# 4layer_schematic.net
KiCad netlist of a schematic drawn in Altium Designer
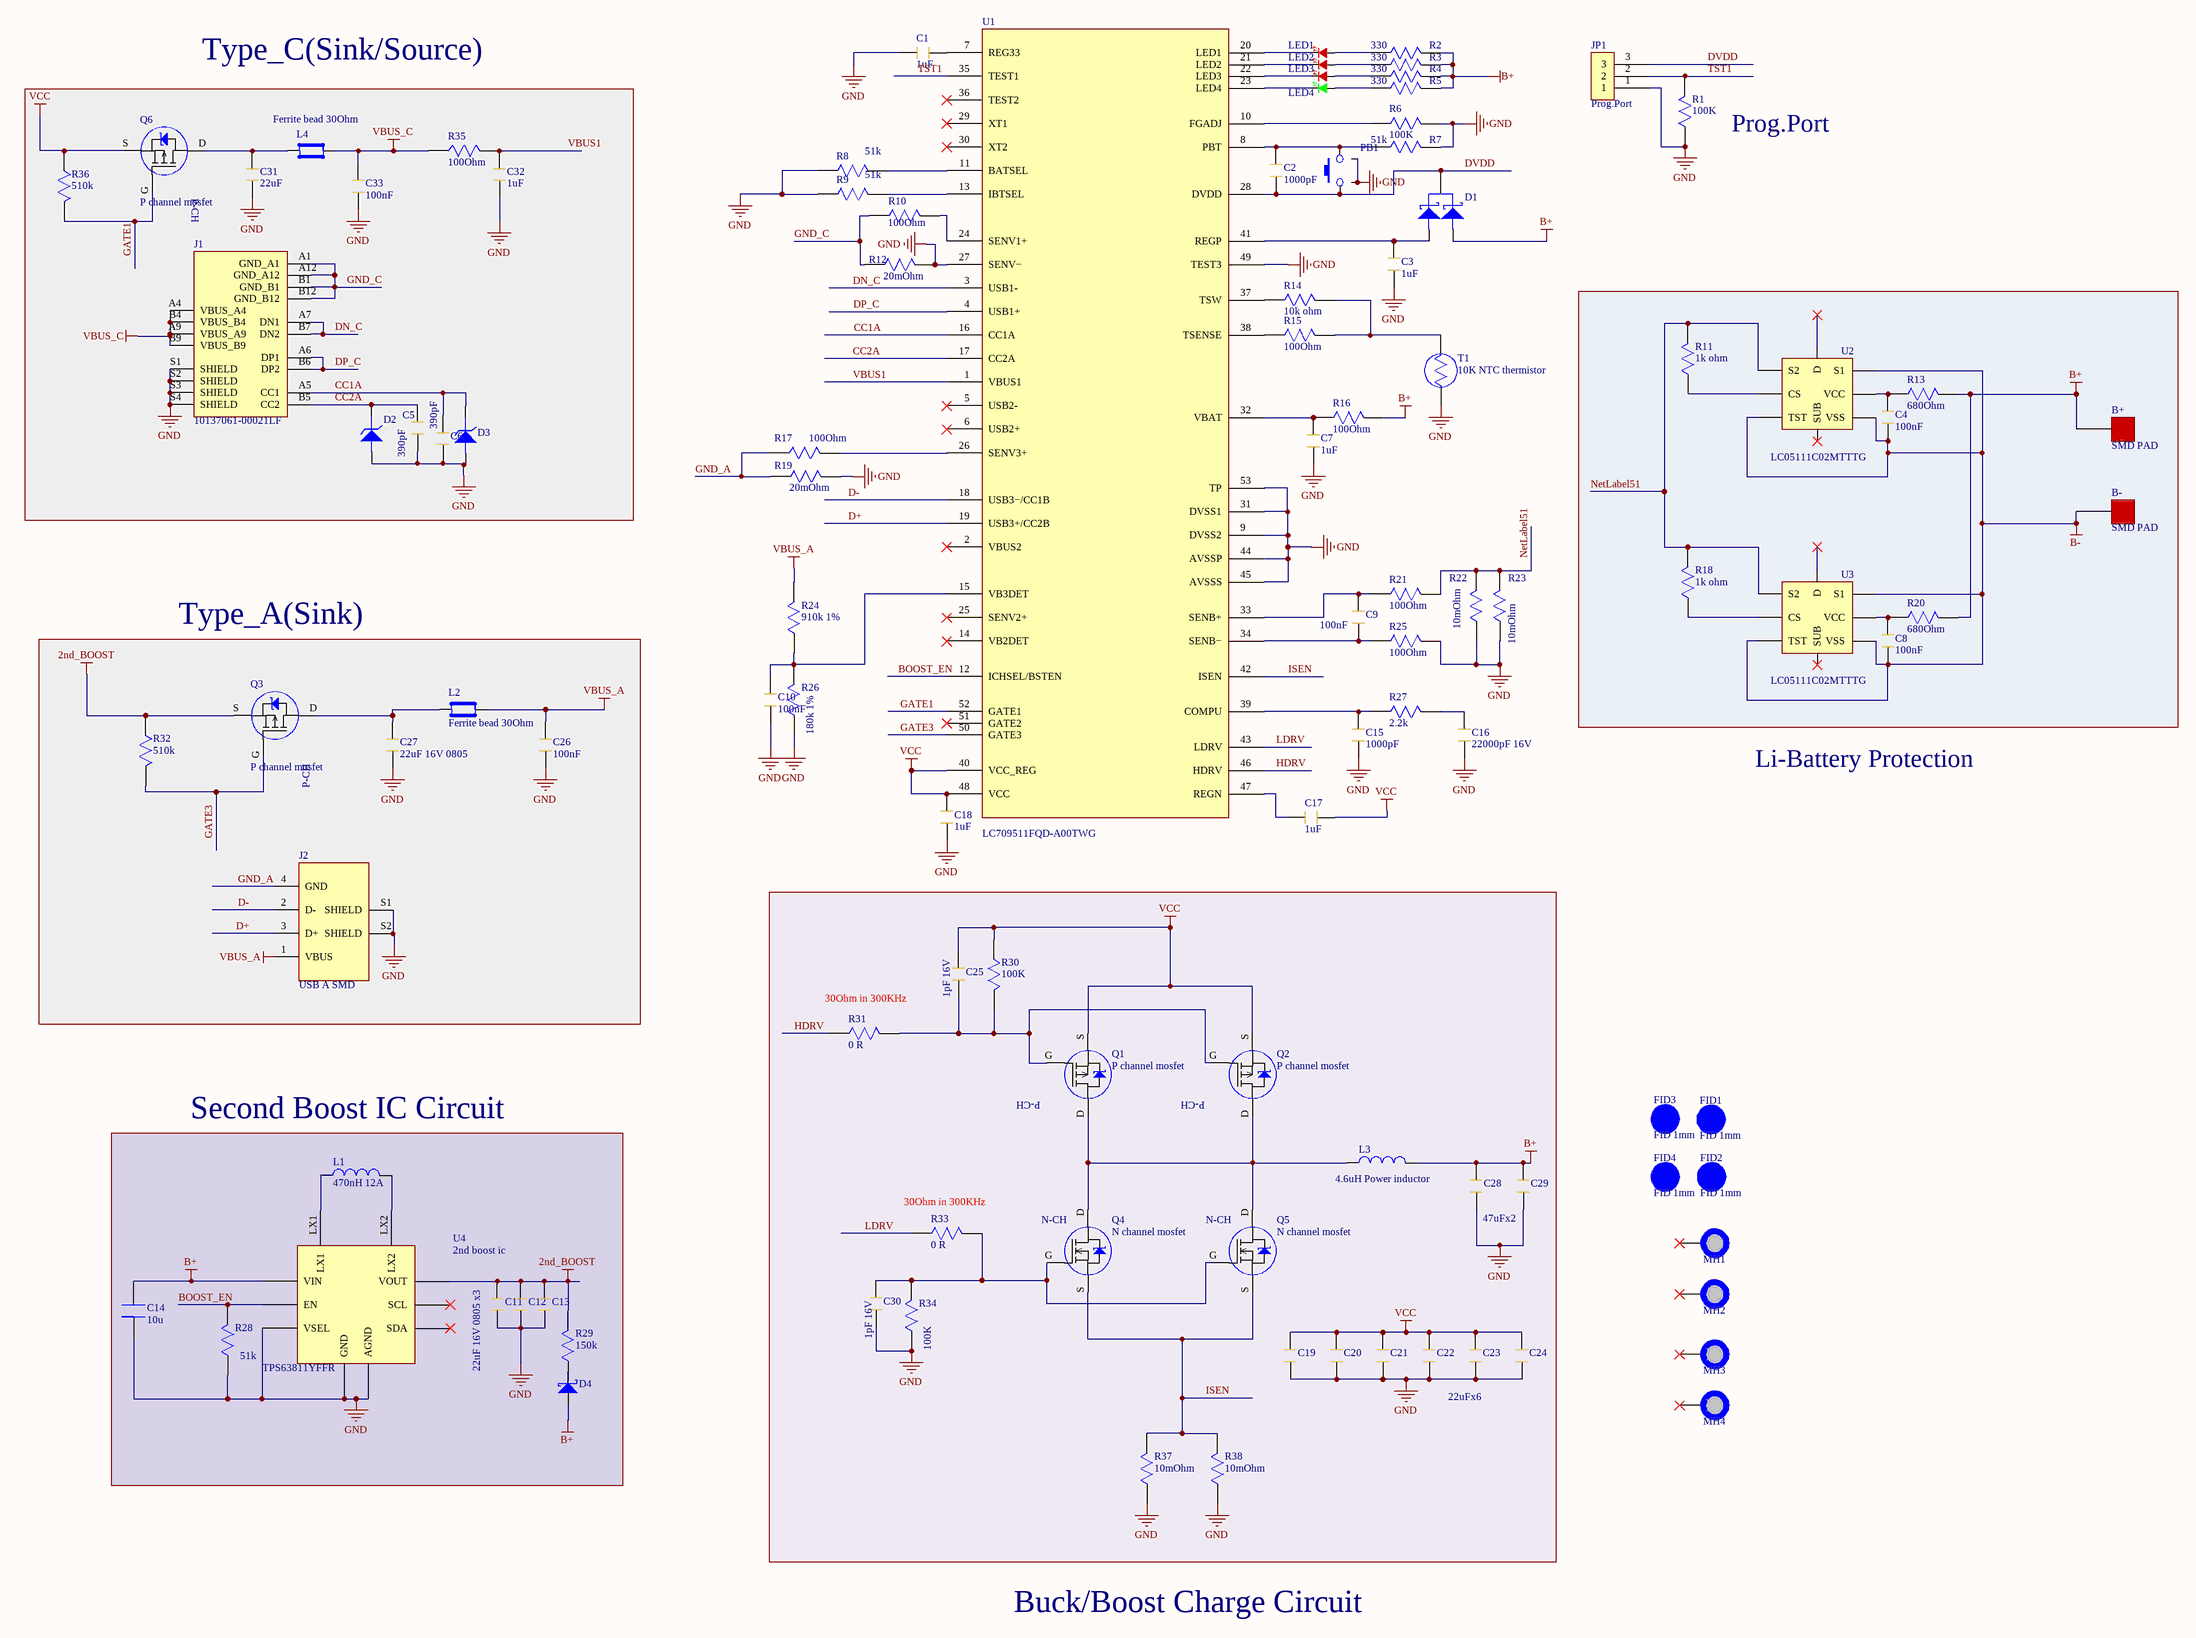
[diagram p0: 4layer schematic.SchDoc]

(export (version "E")
  (design (tool "Eeschema 10.0.6"))
  (components
    (comp (ref "B+")
      (value "SMD PAD")
      (footprint "SMD PAD")
      (libsource (lib "SchlibUltimate (2)") (part "SMD PAD"))
    )
    (comp (ref "B-")
      (value "SMD PAD")
      (footprint "SMD PAD")
      (libsource (lib "SchlibUltimate (2)") (part "SMD PAD"))
    )
    (comp (ref "C1")
      (value "1uF")
      (footprint "R0603")
      (description "Cap Ceramic 1uF 16V Y5V -20% to 80% SMD 0603 85C T/R")
      (fields (field (name "TOLERANCE") "80%"))
      (libsource (lib "SchlibUltimate (2)") (part "1uF cap"))
    )
    (comp (ref "C2")
      (value "1000pF")
      (footprint "C0402")
      (description "Cap Ceramic 0.001uF 16V X7R 10% Pad SMD 0402 125C T/R")
      (fields (field (name "TOLERANCE") "10%"))
      (libsource (lib "SchlibUltimate (2)") (part "1000pF cap"))
    )
    (comp (ref "C3")
      (value "1uF")
      (footprint "R0603")
      (description "Cap Ceramic 1uF 16V Y5V -20% to 80% SMD 0603 85C T/R")
      (fields (field (name "TOLERANCE") "80%"))
      (libsource (lib "SchlibUltimate (2)") (part "1uF cap"))
    )
    (comp (ref "C4")
      (value "100nF")
      (footprint "C0402")
      (description "Cap Ceramic 0.1uF 16V X7R 10% SMD 0402 125C Paper T/R")
      (fields (field (name "TOLERANCE") "10%"))
      (libsource (lib "SchlibUltimate (2)") (part "0.1uF cap"))
    )
    (comp (ref "C5")
      (value "390pF")
      (footprint "R0603")
      (description "Cap Ceramic 390pF 16V X7R 10% SMD 0201 125C Paper T/R")
      (fields (field (name "TOLERANCE") "10%"))
      (libsource (lib "SchlibUltimate (2)") (part "390pF smd cap"))
    )
    (comp (ref "C6")
      (value "390pF")
      (footprint "R0603")
      (description "Cap Ceramic 390pF 16V X7R 10% SMD 0201 125C Paper T/R")
      (fields (field (name "TOLERANCE") "10%"))
      (libsource (lib "SchlibUltimate (2)") (part "390pF smd cap"))
    )
    (comp (ref "C7")
      (value "1uF")
      (footprint "R0603")
      (description "Cap Ceramic 1uF 16V Y5V -20% to 80% SMD 0603 85C T/R")
      (fields (field (name "TOLERANCE") "80%"))
      (libsource (lib "SchlibUltimate (2)") (part "1uF cap"))
    )
    (comp (ref "C8")
      (value "100nF")
      (footprint "C0402")
      (description "Cap Ceramic 0.1uF 16V X7R 10% SMD 0402 125C Paper T/R")
      (fields (field (name "TOLERANCE") "10%"))
      (libsource (lib "SchlibUltimate (2)") (part "0.1uF cap"))
    )
    (comp (ref "C9")
      (value "100nF")
      (footprint "C0402")
      (description "Cap Ceramic 0.1uF 16V X7R 10% SMD 0402 125C Paper T/R")
      (fields (field (name "TOLERANCE") "10%"))
      (libsource (lib "SchlibUltimate (2)") (part "0.1uF cap"))
    )
    (comp (ref "C10")
      (value "100nF")
      (footprint "C0402")
      (description "Cap Ceramic 0.1uF 16V X7R 10% SMD 0402 125C Paper T/R")
      (fields (field (name "TOLERANCE") "10%"))
      (libsource (lib "SchlibUltimate (2)") (part "0.1uF cap"))
    )
    (comp (ref "C11")
      (value "22uF 16V 0805")
      (footprint "Cap 0805")
      (description "Cap Ceramic 22uF 16V X5R 20% Pad SMD 0805 85C T/R")
      (libsource (lib "SchlibUltimate (2)") (part "GRM21BR61C226ME44L"))
    )
    (comp (ref "C12")
      (value "22uF 16V 0805")
      (footprint "Cap 0805")
      (description "Cap Ceramic 22uF 16V X5R 20% Pad SMD 0805 85C T/R")
      (libsource (lib "SchlibUltimate (2)") (part "GRM21BR61C226ME44L"))
    )
    (comp (ref "C13")
      (value "22uF 16V 0805 x3")
      (footprint "Cap 0805")
      (description "Cap Ceramic 22uF 16V X5R 20% Pad SMD 0805 85C T/R")
      (libsource (lib "SchlibUltimate (2)") (part "GRM21BR61C226ME44L"))
    )
    (comp (ref "C14")
      (value "10u")
      (footprint "Cap 0805")
      (description "CAP CER 10UF 16V X5R 0805")
      (fields (field (name "TOLERANCE") "20%"))
      (libsource (lib "SchlibUltimate (2)") (part "C2012X5R1C106M125AC"))
    )
    (comp (ref "C15")
      (value "1000pF")
      (footprint "C0402")
      (description "Cap Ceramic 0.001uF 16V X7R 10% Pad SMD 0402 125C T/R")
      (fields (field (name "TOLERANCE") "10%"))
      (libsource (lib "SchlibUltimate (2)") (part "1000pF cap"))
    )
    (comp (ref "C16")
      (value "22000pF 16V")
      (footprint "C0402")
      (fields (field (name "TOLERANCE") "10%"))
      (libsource (lib "SchlibUltimate (2)") (part "22000pF cap"))
    )
    (comp (ref "C17")
      (value "1uF")
      (footprint "R0603")
      (description "Cap Ceramic 1uF 16V Y5V -20% to 80% SMD 0603 85C T/R")
      (fields (field (name "TOLERANCE") "80%"))
      (libsource (lib "SchlibUltimate (2)") (part "1uF cap"))
    )
    (comp (ref "C18")
      (value "1uF")
      (footprint "R0603")
      (description "Cap Ceramic 1uF 16V Y5V -20% to 80% SMD 0603 85C T/R")
      (fields (field (name "TOLERANCE") "80%"))
      (libsource (lib "SchlibUltimate (2)") (part "1uF cap"))
    )
    (comp (ref "C19")
      (value "22uF 16V 0805")
      (footprint "Cap 0805")
      (description "Cap Ceramic 22uF 16V X5R 20% Pad SMD 0805 85C T/R")
      (libsource (lib "SchlibUltimate (2)") (part "GRM21BR61C226ME44L"))
    )
    (comp (ref "C20")
      (value "22uF 16V 0805")
      (footprint "Cap 0805")
      (description "Cap Ceramic 22uF 16V X5R 20% Pad SMD 0805 85C T/R")
      (libsource (lib "SchlibUltimate (2)") (part "GRM21BR61C226ME44L"))
    )
    (comp (ref "C21")
      (value "22uF 16V 0805")
      (footprint "Cap 0805")
      (description "Cap Ceramic 22uF 16V X5R 20% Pad SMD 0805 85C T/R")
      (libsource (lib "SchlibUltimate (2)") (part "GRM21BR61C226ME44L"))
    )
    (comp (ref "C22")
      (value "22uF 16V 0805")
      (footprint "Cap 0805")
      (description "Cap Ceramic 22uF 16V X5R 20% Pad SMD 0805 85C T/R")
      (libsource (lib "SchlibUltimate (2)") (part "GRM21BR61C226ME44L"))
    )
    (comp (ref "C23")
      (value "22uF 16V 0805")
      (footprint "Cap 0805")
      (description "Cap Ceramic 22uF 16V X5R 20% Pad SMD 0805 85C T/R")
      (libsource (lib "SchlibUltimate (2)") (part "GRM21BR61C226ME44L"))
    )
    (comp (ref "C24")
      (value "22uF 16V 0805")
      (footprint "Cap 0805")
      (description "Cap Ceramic 22uF 16V X5R 20% Pad SMD 0805 85C T/R")
      (libsource (lib "SchlibUltimate (2)") (part "GRM21BR61C226ME44L"))
    )
    (comp (ref "C25")
      (value "1pF 16V")
      (footprint "C0402")
      (description "WURTH ELEKTRONIK - 885012005019 - CAP, 1PF, 16V, C0G/NP0, 0402")
      (libsource (lib "SchlibUltimate (2)") (part "1pF 16V cap"))
    )
    (comp (ref "C26")
      (value "100nF")
      (footprint "Cap 0805")
      (description "CAP CER 0.1UF 50V X7R 0805")
      (fields (field (name "TOLERANCE") "10%") (field (name "VOLTAGE") "50V"))
      (libsource (lib "SchlibUltimate (2)") (part "C2012X7R1H104K085AA"))
    )
    (comp (ref "C27")
      (value "22uF 16V 0805")
      (footprint "Cap 0805")
      (description "Cap Ceramic 22uF 16V X5R 20% Pad SMD 0805 85C T/R")
      (libsource (lib "SchlibUltimate (2)") (part "GRM21BR61C226ME44L"))
    )
    (comp (ref "C28")
      (value "47uFx2")
      (footprint "C1210")
      (description "KEMET - C1210C476M4PACTU. - CAPACITOR CERAMIC 47UF, 16V, X5R, 1210")
      (fields (field (name "TOLERANCE") "20%") (field (name "VOLTAGE") "16V"))
      (libsource (lib "SchlibUltimate (2)") (part "47uF cap"))
    )
    (comp (ref "C29")
      (value "47uF 16V")
      (footprint "C1210")
      (description "KEMET - C1210C476M4PACTU. - CAPACITOR CERAMIC 47UF, 16V, X5R, 1210")
      (fields (field (name "TOLERANCE") "20%") (field (name "VOLTAGE") "16V"))
      (libsource (lib "SchlibUltimate (2)") (part "47uF cap"))
    )
    (comp (ref "C30")
      (value "1pF 16V")
      (footprint "C0402")
      (description "WURTH ELEKTRONIK - 885012005019 - CAP, 1PF, 16V, C0G/NP0, 0402")
      (libsource (lib "SchlibUltimate (2)") (part "1pF 16V cap"))
    )
    (comp (ref "C31")
      (value "22uF")
      (footprint "Cap 0805")
      (description "Cap Ceramic 22uF 16V X5R 20% Pad SMD 0805 85C T/R")
      (libsource (lib "SchlibUltimate (2)") (part "GRM21BR61C226ME44L"))
    )
    (comp (ref "C32")
      (value "1uF")
      (footprint "R0603")
      (description "Cap Ceramic 1uF 16V Y5V -20% to 80% SMD 0603 85C T/R")
      (fields (field (name "TOLERANCE") "80%"))
      (libsource (lib "SchlibUltimate (2)") (part "1uF cap"))
    )
    (comp (ref "C33")
      (value "100nF")
      (footprint "Cap 0805")
      (description "CAP CER 0.1UF 50V X7R 0805")
      (fields (field (name "TOLERANCE") "10%") (field (name "VOLTAGE") "50V"))
      (libsource (lib "SchlibUltimate (2)") (part "C2012X7R1H104K085AA"))
    )
    (comp (ref "D1")
      (value "common cathode Schottkey")
      (footprint "3Pins schottkey")
      (description "Diode Schottky 30V 0.2A 3-Pin SOT-23 T/R")
      (libsource (lib "SchlibUltimate (2)") (part "3pins schottkey common cathode"))
    )
    (comp (ref "D2")
      (value "zener SOD532 5.1V 10mA")
      (footprint "Zener SOD532")
      (fields (field (name "TOLERANCE") "6%"))
      (libsource (lib "SchlibUltimate (2)") (part "MM5Z5V1T1G"))
    )
    (comp (ref "D3")
      (value "zener SOD532 5.1V 10mA")
      (footprint "Zener SOD532")
      (fields (field (name "TOLERANCE") "6%"))
      (libsource (lib "SchlibUltimate (2)") (part "MM5Z5V1T1G"))
    )
    (comp (ref "D4")
      (value "BAT54HT1G")
      (footprint "diode sfmntd")
      (description "DIODE SCHOTTKY 30V 200MA SOD323")
      (libsource (lib "SchlibUltimate (2)") (part "BAT54HT1G"))
    )
    (comp (ref "FID1")
      (value "FID 1mm")
      (footprint "FID")
      (libsource (lib "SchlibUltimate (2)") (part "FID 1mm"))
    )
    (comp (ref "FID2")
      (value "FID 1mm")
      (footprint "FID")
      (libsource (lib "SchlibUltimate (2)") (part "FID 1mm"))
    )
    (comp (ref "FID3")
      (value "FID 1mm")
      (footprint "FID")
      (libsource (lib "SchlibUltimate (2)") (part "FID 1mm"))
    )
    (comp (ref "FID4")
      (value "FID 1mm")
      (footprint "FID")
      (libsource (lib "SchlibUltimate (2)") (part "FID 1mm"))
    )
    (comp (ref "J1")
      (value "10137061-00021LF")
      (footprint "PCBComponent_1")
      (description "Conn USB 3.1 Type C RCP 24 POS 0.5mm Solder RA SMF 24 Terminal 1 Port T/R")
      (libsource (lib "SchlibUltimate (2)") (part "10137061-00021LF"))
    )
    (comp (ref "J2")
      (value "USB A SMD")
      (footprint "692122030100")
      (description "Socket, angled USB 3.0 A   9 P, 692122030100, Würth Elektronik")
      (libsource (lib "SchlibUltimate (2)") (part "USB A SMD"))
    )
    (comp (ref "JP1")
      (value "Prog.Port")
      (footprint "HDR Male 1x3")
      (description "CONN HEADER VERT 3POS 2.54MM")
      (libsource (lib "SchlibUltimate (2)") (part "68000-103HLF"))
    )
    (comp (ref "L1")
      (value "470nH 12A")
      (footprint "inductor 470nH")
      (libsource (lib "SchlibUltimate (2)") (part "470nH ind"))
    )
    (comp (ref "L2")
      (value "Ferrite bead 30Ohm")
      (footprint "R0805")
      (description "Ferrite Beads Multi-Layer 30Ohm 100MHz 4A 14mOhm DCR 0805 T/R")
      (fields (field (name "TOLERANCE") "25%"))
      (libsource (lib "SchlibUltimate (2)") (part "BLM21PG300SN1D"))
    )
    (comp (ref "L3")
      (value "4.6uH Power inductor")
      (footprint "inductor mouser")
      (description "FIXED IND 4.6UH 9.1A 13.8 MOHM")
      (fields (field (name "TOLERANCE") "30%"))
      (libsource (lib "SchlibUltimate (2)") (part "CDRH127/LDNP-4R6NC"))
    )
    (comp (ref "L4")
      (value "Ferrite bead 30Ohm")
      (footprint "R0805")
      (description "Ferrite Beads Multi-Layer 30Ohm 100MHz 4A 14mOhm DCR 0805 T/R")
      (fields (field (name "TOLERANCE") "25%"))
      (libsource (lib "SchlibUltimate (2)") (part "BLM21PG300SN1D"))
    )
    (comp (ref "LED1")
      (value "RED SMD")
      (footprint "ORNG LED SMD 1206")
      (description "LED RED CLEAR 1206 SMD")
      (libsource (lib "SchlibUltimate (2)") (part "SMLLX1206ICTR"))
    )
    (comp (ref "LED2")
      (value "RED SMD")
      (footprint "ORNG LED SMD 1206")
      (description "LED RED CLEAR 1206 SMD")
      (libsource (lib "SchlibUltimate (2)") (part "SMLLX1206ICTR"))
    )
    (comp (ref "LED3")
      (value "RED SMD")
      (footprint "ORNG LED SMD 1206")
      (description "LED RED CLEAR 1206 SMD")
      (libsource (lib "SchlibUltimate (2)") (part "SMLLX1206ICTR"))
    )
    (comp (ref "LED4")
      (value "GRN SMD")
      (footprint "GRN SMD LED")
      (description "Led Green SMD")
      (libsource (lib "SchlibUltimate (2)") (part "LNJ311G83RA"))
    )
    (comp (ref "MH1")
      (value "Mount holes")
      (footprint "MH")
      (libsource (lib "SchlibUltimate (2)") (part "Mount holes"))
    )
    (comp (ref "MH2")
      (value "Mount holes")
      (footprint "MH")
      (libsource (lib "SchlibUltimate (2)") (part "Mount holes"))
    )
    (comp (ref "MH3")
      (value "MH. not plated")
      (footprint "MH. not plated")
      (libsource (lib "SchlibUltimate (2)") (part "MH. not plated"))
    )
    (comp (ref "MH4")
      (value "MH. not plated")
      (footprint "MH. not plated")
      (libsource (lib "SchlibUltimate (2)") (part "MH. not plated"))
    )
    (comp (ref "PB1")
      (value "FSMRA4JH04")
      (footprint "PB Right angle through hole")
      (description "TE CONNECTIVITY - FSMRA4JH04 - SWITCH, TACT, SPST")
      (libsource (lib "SchlibUltimate (2)") (part "FSMRA4JH04"))
    )
    (comp (ref "Q1")
      (value "P channel mosfet")
      (footprint "ECH8310-TL-H")
      (description "Trans MOSFET P-CH 30V 9A 8-Pin ECH T/R")
      (libsource (lib "SchlibUltimate (2)") (part "ECH8310-TL-H"))
    )
    (comp (ref "Q2")
      (value "P channel mosfet")
      (footprint "ECH8310-TL-H")
      (description "Trans MOSFET P-CH 30V 9A 8-Pin ECH T/R")
      (libsource (lib "SchlibUltimate (2)") (part "ECH8310-TL-H"))
    )
    (comp (ref "Q3")
      (value "P channel mosfet")
      (footprint "ECH8310-TL-H")
      (description "Trans MOSFET P-CH 30V 9A 8-Pin ECH T/R")
      (libsource (lib "SchlibUltimate (2)") (part "ECH8310-TL-H"))
    )
    (comp (ref "Q4")
      (value "N channel mosfet")
      (footprint "Power mosfet on semi")
      (description "Single N−Channel Power MOSFET 25V, 94A, 3.3mΩ")
      (libsource (lib "SchlibUltimate (2)") (part "NTTFS4H05NTAG"))
    )
    (comp (ref "Q5")
      (value "N channel mosfet")
      (footprint "Power mosfet on semi")
      (description "Single N−Channel Power MOSFET 25V, 94A, 3.3mΩ")
      (libsource (lib "SchlibUltimate (2)") (part "NTTFS4H05NTAG"))
    )
    (comp (ref "Q6")
      (value "P channel mosfet")
      (footprint "ECH8310-TL-H")
      (description "Trans MOSFET P-CH 30V 9A 8-Pin ECH T/R")
      (libsource (lib "SchlibUltimate (2)") (part "ECH8310-TL-H"))
    )
    (comp (ref "R1")
      (value "100K")
      (footprint "R0805")
      (description "RES SMD 100K OHM 1% 1/8W 0805")
      (fields (field (name "TOLERANCE") "1%"))
      (libsource (lib "SchlibUltimate (2)") (part "RC0805FR-07100KL"))
    )
    (comp (ref "R2")
      (value "330")
      (footprint "R0805")
      (description "YAGEO   RC0805JR-07330RL   THICK FILM RESISTOR, 330 OHM, 125mW, 5%, FULL REEL")
      (fields (field (name "TOLERANCE") "5%"))
      (libsource (lib "SchlibUltimate (2)") (part "RC0805JR-07330RL"))
    )
    (comp (ref "R3")
      (value "330")
      (footprint "R0805")
      (description "YAGEO   RC0805JR-07330RL   THICK FILM RESISTOR, 330 OHM, 125mW, 5%, FULL REEL")
      (fields (field (name "TOLERANCE") "5%"))
      (libsource (lib "SchlibUltimate (2)") (part "RC0805JR-07330RL"))
    )
    (comp (ref "R4")
      (value "330")
      (footprint "R0805")
      (description "YAGEO   RC0805JR-07330RL   THICK FILM RESISTOR, 330 OHM, 125mW, 5%, FULL REEL")
      (fields (field (name "TOLERANCE") "5%"))
      (libsource (lib "SchlibUltimate (2)") (part "RC0805JR-07330RL"))
    )
    (comp (ref "R5")
      (value "330")
      (footprint "R0805")
      (description "YAGEO   RC0805JR-07330RL   THICK FILM RESISTOR, 330 OHM, 125mW, 5%, FULL REEL")
      (fields (field (name "TOLERANCE") "5%"))
      (libsource (lib "SchlibUltimate (2)") (part "RC0805JR-07330RL"))
    )
    (comp (ref "R6")
      (value "100K")
      (footprint "R0805")
      (description "RES SMD 100K OHM 1% 1/8W 0805")
      (fields (field (name "TOLERANCE") "1%"))
      (libsource (lib "SchlibUltimate (2)") (part "RC0805FR-07100KL"))
    )
    (comp (ref "R7")
      (value "51k")
      (footprint "R0805")
      (fields (field (name "TOLERANCE") "5%"))
      (libsource (lib "SchlibUltimate (2)") (part "CRCW080551K0JNEA"))
    )
    (comp (ref "R8")
      (value "51k")
      (footprint "R0805")
      (fields (field (name "TOLERANCE") "5%"))
      (libsource (lib "SchlibUltimate (2)") (part "CRCW080551K0JNEA"))
    )
    (comp (ref "R9")
      (value "51k")
      (footprint "R0805")
      (fields (field (name "TOLERANCE") "5%"))
      (libsource (lib "SchlibUltimate (2)") (part "CRCW080551K0JNEA"))
    )
    (comp (ref "R10")
      (value "100Ohm")
      (footprint "R0603")
      (fields (field (name "TOLERANCE") "5%"))
      (libsource (lib "SchlibUltimate (2)") (part "ESR03EZPJ101"))
    )
    (comp (ref "R11")
      (value "1k ohm")
      (footprint "R0805")
      (description "RES SMD 1K OHM 1% 1/8W 0805")
      (fields (field (name "TOLERANCE") "1%"))
      (libsource (lib "SchlibUltimate (2)") (part "RC0805FR-071KL"))
    )
    (comp (ref "R12")
      (value "20mOhm")
      (footprint "R1206")
      (fields (field (name "TOLERANCE") "1%"))
      (libsource (lib "SchlibUltimate (2)") (part "ERJ8CWFR020V"))
    )
    (comp (ref "R13")
      (value "680Ohm")
      (footprint "R0805")
      (fields (field (name "TOLERANCE") "1%"))
      (libsource (lib "SchlibUltimate (2)") (part "680Ohm 1/8 watt"))
    )
    (comp (ref "R14")
      (value "10k ohm")
      (footprint "R0805")
      (description "RES SMD 10K OHM 1% 1/8W 0805")
      (fields (field (name "TOLERANCE") "1%"))
      (libsource (lib "SchlibUltimate (2)") (part "RC0805FR-0710KL"))
    )
    (comp (ref "R15")
      (value "100Ohm")
      (footprint "R0603")
      (fields (field (name "TOLERANCE") "5%"))
      (libsource (lib "SchlibUltimate (2)") (part "ESR03EZPJ101"))
    )
    (comp (ref "R16")
      (value "100Ohm")
      (footprint "R0603")
      (fields (field (name "TOLERANCE") "5%"))
      (libsource (lib "SchlibUltimate (2)") (part "ESR03EZPJ101"))
    )
    (comp (ref "R17")
      (value "100Ohm")
      (footprint "R0603")
      (fields (field (name "TOLERANCE") "5%"))
      (libsource (lib "SchlibUltimate (2)") (part "ESR03EZPJ101"))
    )
    (comp (ref "R18")
      (value "1k ohm")
      (footprint "R0805")
      (description "RES SMD 1K OHM 1% 1/8W 0805")
      (fields (field (name "TOLERANCE") "1%"))
      (libsource (lib "SchlibUltimate (2)") (part "RC0805FR-071KL"))
    )
    (comp (ref "R19")
      (value "20mOhm")
      (footprint "R1206")
      (fields (field (name "TOLERANCE") "1%"))
      (libsource (lib "SchlibUltimate (2)") (part "ERJ8CWFR020V"))
    )
    (comp (ref "R20")
      (value "680Ohm")
      (footprint "R0805")
      (fields (field (name "TOLERANCE") "1%"))
      (libsource (lib "SchlibUltimate (2)") (part "680Ohm 1/8 watt"))
    )
    (comp (ref "R21")
      (value "100Ohm")
      (footprint "R0603")
      (fields (field (name "TOLERANCE") "5%"))
      (libsource (lib "SchlibUltimate (2)") (part "ESR03EZPJ101"))
    )
    (comp (ref "R22")
      (value "10mOhm")
      (footprint "R1206")
      (fields (field (name "TOLERANCE") "1%"))
      (libsource (lib "SchlibUltimate (2)") (part "ERJ-8BWFR010V"))
    )
    (comp (ref "R23")
      (value "10mOhm")
      (footprint "R1206")
      (fields (field (name "TOLERANCE") "1%"))
      (libsource (lib "SchlibUltimate (2)") (part "ERJ-8BWFR010V"))
    )
    (comp (ref "R24")
      (value "910k 1%")
      (footprint "R0805")
      (description "Res Thick Film 0805 9.1K Ohm 1% 1/8W +/-100ppm/ßC Molded SMD Punched Carrier T/R")
      (fields (field (name "TOLERANCE") "1%"))
      (libsource (lib "SchlibUltimate (2)") (part "ERJ-6ENF9101V"))
    )
    (comp (ref "R25")
      (value "100Ohm")
      (footprint "R0603")
      (fields (field (name "TOLERANCE") "5%"))
      (libsource (lib "SchlibUltimate (2)") (part "ESR03EZPJ101"))
    )
    (comp (ref "R26")
      (value "180k 1%")
      (footprint "R0805")
      (description "Thick Film Resistors - SMD 0805 180Kohms 1% AEC-Q200")
      (fields (field (name "TOLERANCE") "1%"))
      (libsource (lib "SchlibUltimate (2)") (part "ERJ-6ENF1803V"))
    )
    (comp (ref "R27")
      (value "2.2k")
      (footprint "R0805")
      (description "RESISTOR, THICK FILM, 2.2KOHM, 125mW, 1%, FULL REEL")
      (fields (field (name "TOLERANCE") "1%"))
      (libsource (lib "SchlibUltimate (2)") (part "RC0805FR-072K2L"))
    )
    (comp (ref "R28")
      (value "51k")
      (footprint "R0805")
      (fields (field (name "TOLERANCE") "5%"))
      (libsource (lib "SchlibUltimate (2)") (part "CRCW080551K0JNEA"))
    )
    (comp (ref "R29")
      (value "150k")
      (footprint "R0805")
      (description "RES SMD 150K OHM 5% 1/8W 0805")
      (fields (field (name "TOLERANCE") "5%"))
      (libsource (lib "SchlibUltimate (2)") (part "ERJ-6GEYJ154V"))
    )
    (comp (ref "R30")
      (value "100K")
      (footprint "R0805")
      (description "RES SMD 100K OHM 1% 1/8W 0805")
      (fields (field (name "TOLERANCE") "1%"))
      (libsource (lib "SchlibUltimate (2)") (part "RC0805FR-07100KL"))
    )
    (comp (ref "R31")
      (value "0 R")
      (footprint "R0805")
      (description "RES SMD 0 OHM JUMPER 1/8W 0805")
      (fields (field (name "TOLERANCE") "5%"))
      (libsource (lib "SchlibUltimate (2)") (part "RC0805JR-070RL"))
    )
    (comp (ref "R32")
      (value "510k")
      (footprint "R0805")
      (description "RES SMD 510K OHM 5% 1/8W 0805")
      (fields (field (name "TOLERANCE") "5%"))
      (libsource (lib "SchlibUltimate (2)") (part "ERJ-6GEYJ514V"))
    )
    (comp (ref "R33")
      (value "0 R")
      (footprint "R0805")
      (description "RES SMD 0 OHM JUMPER 1/8W 0805")
      (fields (field (name "TOLERANCE") "5%"))
      (libsource (lib "SchlibUltimate (2)") (part "RC0805JR-070RL"))
    )
    (comp (ref "R34")
      (value "100K")
      (footprint "R0805")
      (description "RES SMD 100K OHM 1% 1/8W 0805")
      (fields (field (name "TOLERANCE") "1%"))
      (libsource (lib "SchlibUltimate (2)") (part "RC0805FR-07100KL"))
    )
    (comp (ref "R35")
      (value "100Ohm")
      (footprint "R0603")
      (fields (field (name "TOLERANCE") "5%"))
      (libsource (lib "SchlibUltimate (2)") (part "ESR03EZPJ101"))
    )
    (comp (ref "R36")
      (value "510k")
      (footprint "R0805")
      (description "RES SMD 510K OHM 5% 1/8W 0805")
      (fields (field (name "TOLERANCE") "5%"))
      (libsource (lib "SchlibUltimate (2)") (part "ERJ-6GEYJ514V"))
    )
    (comp (ref "R37")
      (value "10mOhm")
      (footprint "R1206")
      (fields (field (name "TOLERANCE") "1%"))
      (libsource (lib "SchlibUltimate (2)") (part "ERJ-8BWFR010V"))
    )
    (comp (ref "R38")
      (value "10mOhm")
      (footprint "R1206")
      (fields (field (name "TOLERANCE") "1%"))
      (libsource (lib "SchlibUltimate (2)") (part "ERJ-8BWFR010V"))
    )
    (comp (ref "T1")
      (value "10K NTC thermistor")
      (footprint "thermistor")
      (description "Thermistor, High Sensitivity, NTC, Res 10 Kilohms, Tol +/-2%, Radial, Disc, TC 15Sec.")
      (fields (field (name "TOLERANCE") "2%"))
      (libsource (lib "SchlibUltimate (2)") (part "RL0503-5820-97-MS"))
    )
    (comp (ref "U1")
      (value "LC709511FQD-A00TWG")
      (footprint "Quad52")
      (description "Power Bank Controller, USB Type-C & Quick Charge™ 3.0, for 1-Cell Li-Ion and Li-Poly Battery")
      (fields (field (name "SUPPLIER PART NUMBER 1") "LC709511FQD-A00TWG"))
      (libsource (lib "SchlibUltimate (2)") (part "LC709511FQD-A00TWG"))
    )
    (comp (ref "U2")
      (value "LC05111C02MTTTG")
      (footprint "LC05111C02MTTTGOSCT")
      (description "IC BATT PROTECTION LI-ION 6WDFN")
      (libsource (lib "SchlibUltimate (2)") (part "LC05111C02MTTTG"))
    )
    (comp (ref "U3")
      (value "LC05111C02MTTTG")
      (footprint "LC05111C02MTTTGOSCT")
      (description "IC BATT PROTECTION LI-ION 6WDFN")
      (libsource (lib "SchlibUltimate (2)") (part "LC05111C02MTTTG"))
    )
    (comp (ref "U4")
      (value "2nd boost ic")
      (footprint "BGA3x5")
      (description "Switching mode BUCK/BOOST IC")
      (libsource (lib "SchlibUltimate (2)") (part "TPS63811YFFR"))
    )
  )
  (nets
    (net (code "1") (name "/BOOST_EN") (class "Default")
      (node (ref "R28") (pin "2") (pinfunction "2_2") (pintype "passive"))
      (node (ref "U1") (pin "12") (pinfunction "ICHSEL/BSTEN_12") (pintype "passive"))
      (node (ref "U4") (pin "EN") (pinfunction "EN_EN") (pintype "passive"))
    )
    (net (code "2") (name "/CC1A") (class "Default")
      (node (ref "C6") (pin "2") (pinfunction "2_2") (pintype "passive"))
      (node (ref "D3") (pin "1") (pinfunction "K_1") (pintype "passive"))
      (node (ref "J1") (pin "A5") (pinfunction "CC1_A5") (pintype "passive"))
      (node (ref "U1") (pin "16") (pinfunction "CC1A_16") (pintype "passive"))
    )
    (net (code "3") (name "/CC2A") (class "Default")
      (node (ref "C5") (pin "2") (pinfunction "2_2") (pintype "passive"))
      (node (ref "D2") (pin "1") (pinfunction "K_1") (pintype "passive"))
      (node (ref "J1") (pin "B5") (pinfunction "CC2_B5") (pintype "passive"))
      (node (ref "U1") (pin "17") (pinfunction "CC2A_17") (pintype "passive"))
    )
    (net (code "4") (name "/D+") (class "Default")
      (node (ref "J2") (pin "3") (pinfunction "D+_3") (pintype "passive"))
      (node (ref "U1") (pin "19") (pinfunction "USB3+/CC2B_19") (pintype "passive"))
    )
    (net (code "5") (name "/D-") (class "Default")
      (node (ref "J2") (pin "2") (pinfunction "D-_2") (pintype "passive"))
      (node (ref "U1") (pin "18") (pinfunction "USB3−/CC1B_18") (pintype "passive"))
    )
    (net (code "6") (name "/DN_C") (class "Default")
      (node (ref "J1") (pin "A7") (pinfunction "DN1_A7") (pintype "passive"))
      (node (ref "J1") (pin "B7") (pinfunction "DN2_B7") (pintype "passive"))
      (node (ref "U1") (pin "3") (pinfunction "USB1-_3") (pintype "passive"))
    )
    (net (code "7") (name "/DP_C") (class "Default")
      (node (ref "J1") (pin "A6") (pinfunction "DP1_A6") (pintype "passive"))
      (node (ref "J1") (pin "B6") (pinfunction "DP2_B6") (pintype "passive"))
      (node (ref "U1") (pin "4") (pinfunction "USB1+_4") (pintype "passive"))
    )
    (net (code "8") (name "/DVDD") (class "Default")
      (node (ref "C2") (pin "1") (pinfunction "1_1") (pintype "passive"))
      (node (ref "D1") (pin "3") (pinfunction "Cathode_3") (pintype "passive"))
      (node (ref "JP1") (pin "3") (pinfunction "3_3") (pintype "passive"))
      (node (ref "PB1") (pin "1") (pinfunction "1_1") (pintype "passive"))
      (node (ref "U1") (pin "28") (pinfunction "DVDD_28") (pintype "passive"))
    )
    (net (code "9") (name "/GATE1") (class "Default")
      (node (ref "Q6") (pin "G") (pinfunction "G_G") (pintype "passive"))
      (node (ref "R36") (pin "1") (pinfunction "1_1") (pintype "passive"))
      (node (ref "U1") (pin "52") (pinfunction "GATE1_52") (pintype "passive"))
    )
    (net (code "10") (name "/GATE3") (class "Default")
      (node (ref "Q3") (pin "G") (pinfunction "G_G") (pintype "passive"))
      (node (ref "R32") (pin "1") (pinfunction "1_1") (pintype "passive"))
      (node (ref "U1") (pin "50") (pinfunction "GATE3_50") (pintype "passive"))
    )
    (net (code "11") (name "/GND_A") (class "Default")
      (node (ref "J2") (pin "4") (pinfunction "GND_4") (pintype "passive"))
      (node (ref "R17") (pin "1") (pinfunction "1_1") (pintype "passive"))
      (node (ref "R19") (pin "1") (pinfunction "1_1") (pintype "passive"))
    )
    (net (code "12") (name "/GND_C") (class "Default")
      (node (ref "J1") (pin "A1") (pinfunction "GND_A1_A1") (pintype "passive"))
      (node (ref "J1") (pin "A12") (pinfunction "GND_A12_A12") (pintype "passive"))
      (node (ref "J1") (pin "B1") (pinfunction "GND_B1_B1") (pintype "passive"))
      (node (ref "J1") (pin "B12") (pinfunction "GND_B12_B12") (pintype "passive"))
      (node (ref "R10") (pin "1") (pinfunction "1_1") (pintype "passive"))
      (node (ref "R12") (pin "1") (pinfunction "1_1") (pintype "passive"))
    )
    (net (code "13") (name "/HDRV") (class "Default")
      (node (ref "R31") (pin "1") (pinfunction "1_1") (pintype "passive"))
      (node (ref "U1") (pin "46") (pinfunction "HDRV_46") (pintype "passive"))
    )
    (net (code "14") (name "/ISEN") (class "Default")
      (node (ref "Q4") (pin "S") (pinfunction "S_S") (pintype "passive"))
      (node (ref "Q5") (pin "S") (pinfunction "S_S") (pintype "passive"))
      (node (ref "R37") (pin "2") (pinfunction "2_2") (pintype "passive"))
      (node (ref "R38") (pin "2") (pinfunction "2_2") (pintype "passive"))
      (node (ref "U1") (pin "42") (pinfunction "ISEN_42") (pintype "passive"))
    )
    (net (code "15") (name "/LDRV") (class "Default")
      (node (ref "R33") (pin "1") (pinfunction "1_1") (pintype "passive"))
      (node (ref "U1") (pin "43") (pinfunction "LDRV_43") (pintype "passive"))
    )
    (net (code "16") (name "/NetLabel51") (class "Default")
      (node (ref "R11") (pin "2") (pinfunction "2_2") (pintype "passive"))
      (node (ref "R18") (pin "2") (pinfunction "2_2") (pintype "passive"))
      (node (ref "R21") (pin "2") (pinfunction "2_2") (pintype "passive"))
      (node (ref "R22") (pin "2") (pinfunction "2_2") (pintype "passive"))
      (node (ref "R23") (pin "2") (pinfunction "2_2") (pintype "passive"))
      (node (ref "U2") (pin "S2") (pinfunction "S2_S2") (pintype "passive"))
      (node (ref "U3") (pin "S2") (pinfunction "S2_S2") (pintype "passive"))
    )
    (net (code "17") (name "/TST1") (class "Default")
      (node (ref "JP1") (pin "2") (pinfunction "2_2") (pintype "passive"))
      (node (ref "R1") (pin "1") (pinfunction "1_1") (pintype "passive"))
      (node (ref "U1") (pin "35") (pinfunction "TEST1_35") (pintype "passive"))
    )
    (net (code "18") (name "/VBUS1") (class "Default")
      (node (ref "C32") (pin "2") (pinfunction "2_2") (pintype "passive"))
      (node (ref "R35") (pin "1") (pinfunction "1_1") (pintype "passive"))
      (node (ref "U1") (pin "1") (pinfunction "VBUS1_1") (pintype "passive"))
    )
    (net (code "19") (name "2nd_BOOST") (class "Default")
      (node (ref "C11") (pin "2") (pinfunction "2_2") (pintype "passive"))
      (node (ref "C12") (pin "2") (pinfunction "2_2") (pintype "passive"))
      (node (ref "C13") (pin "2") (pinfunction "2_2") (pintype "passive"))
      (node (ref "Q3") (pin "S") (pinfunction "S_S") (pintype "passive"))
      (node (ref "R29") (pin "2") (pinfunction "2_2") (pintype "passive"))
      (node (ref "R32") (pin "2") (pinfunction "2_2") (pintype "passive"))
      (node (ref "U4") (pin "VOUT") (pinfunction "VOUT_VOUT") (pintype "passive"))
    )
    (net (code "20") (name "B+") (class "Default")
      (node (ref "B+") (pin "1") (pinfunction "1_1") (pintype "passive"))
      (node (ref "C14") (pin "2") (pinfunction "2_2") (pintype "passive"))
      (node (ref "C28") (pin "2") (pinfunction "2_2") (pintype "passive"))
      (node (ref "C29") (pin "2") (pinfunction "2_2") (pintype "passive"))
      (node (ref "D1") (pin "2") (pinfunction "ANODE2_2") (pintype "passive"))
      (node (ref "D4") (pin "2") (pinfunction "Anode_2") (pintype "passive"))
      (node (ref "L3") (pin "2") (pinfunction "2_2") (pintype "passive"))
      (node (ref "R13") (pin "2") (pinfunction "2_2") (pintype "passive"))
      (node (ref "R16") (pin "2") (pinfunction "2_2") (pintype "passive"))
      (node (ref "R2") (pin "2") (pinfunction "2_2") (pintype "passive"))
      (node (ref "R20") (pin "2") (pinfunction "2_2") (pintype "passive"))
      (node (ref "R3") (pin "2") (pinfunction "2_2") (pintype "passive"))
      (node (ref "R4") (pin "2") (pinfunction "2_2") (pintype "passive"))
      (node (ref "R5") (pin "2") (pinfunction "2_2") (pintype "passive"))
      (node (ref "U4") (pin "VIN") (pinfunction "VIN_VIN") (pintype "passive"))
    )
    (net (code "21") (name "B-") (class "Default")
      (node (ref "B-") (pin "1") (pinfunction "1_1") (pintype "passive"))
      (node (ref "C4") (pin "1") (pinfunction "1_1") (pintype "passive"))
      (node (ref "C8") (pin "1") (pinfunction "1_1") (pintype "passive"))
      (node (ref "U2") (pin "S1") (pinfunction "S1_S1") (pintype "passive"))
      (node (ref "U2") (pin "TST") (pinfunction "TST_TST") (pintype "passive"))
      (node (ref "U2") (pin "VSS") (pinfunction "VSS_VSS") (pintype "passive"))
      (node (ref "U3") (pin "S1") (pinfunction "S1_S1") (pintype "passive"))
      (node (ref "U3") (pin "TST") (pinfunction "TST_TST") (pintype "passive"))
      (node (ref "U3") (pin "VSS") (pinfunction "VSS_VSS") (pintype "passive"))
    )
    (net (code "22") (name "GND") (class "Default")
      (node (ref "C1") (pin "1") (pinfunction "1_1") (pintype "passive"))
      (node (ref "C10") (pin "1") (pinfunction "1_1") (pintype "passive"))
      (node (ref "C11") (pin "1") (pinfunction "1_1") (pintype "passive"))
      (node (ref "C12") (pin "1") (pinfunction "1_1") (pintype "passive"))
      (node (ref "C13") (pin "1") (pinfunction "1_1") (pintype "passive"))
      (node (ref "C14") (pin "1") (pinfunction "1_1") (pintype "passive"))
      (node (ref "C15") (pin "1") (pinfunction "1_1") (pintype "passive"))
      (node (ref "C16") (pin "1") (pinfunction "1_1") (pintype "passive"))
      (node (ref "C18") (pin "1") (pinfunction "1_1") (pintype "passive"))
      (node (ref "C19") (pin "1") (pinfunction "1_1") (pintype "passive"))
      (node (ref "C20") (pin "1") (pinfunction "1_1") (pintype "passive"))
      (node (ref "C21") (pin "1") (pinfunction "1_1") (pintype "passive"))
      (node (ref "C22") (pin "1") (pinfunction "1_1") (pintype "passive"))
      (node (ref "C23") (pin "1") (pinfunction "1_1") (pintype "passive"))
      (node (ref "C24") (pin "1") (pinfunction "1_1") (pintype "passive"))
      (node (ref "C26") (pin "1") (pinfunction "1_1") (pintype "passive"))
      (node (ref "C27") (pin "1") (pinfunction "1_1") (pintype "passive"))
      (node (ref "C28") (pin "1") (pinfunction "1_1") (pintype "passive"))
      (node (ref "C29") (pin "1") (pinfunction "1_1") (pintype "passive"))
      (node (ref "C3") (pin "1") (pinfunction "1_1") (pintype "passive"))
      (node (ref "C30") (pin "1") (pinfunction "1_1") (pintype "passive"))
      (node (ref "C31") (pin "1") (pinfunction "1_1") (pintype "passive"))
      (node (ref "C32") (pin "1") (pinfunction "1_1") (pintype "passive"))
      (node (ref "C33") (pin "1") (pinfunction "1_1") (pintype "passive"))
      (node (ref "C5") (pin "1") (pinfunction "1_1") (pintype "passive"))
      (node (ref "C6") (pin "1") (pinfunction "1_1") (pintype "passive"))
      (node (ref "C7") (pin "1") (pinfunction "1_1") (pintype "passive"))
      (node (ref "D2") (pin "2") (pinfunction "A_2") (pintype "passive"))
      (node (ref "D3") (pin "2") (pinfunction "A_2") (pintype "passive"))
      (node (ref "J1") (pin "S1") (pinfunction "SHIELD_S1") (pintype "passive"))
      (node (ref "J1") (pin "S2") (pinfunction "SHIELD_S2") (pintype "passive"))
      (node (ref "J1") (pin "S3") (pinfunction "SHIELD_S3") (pintype "passive"))
      (node (ref "J1") (pin "S4") (pinfunction "SHIELD_S4") (pintype "passive"))
      (node (ref "J2") (pin "S1") (pinfunction "SHIELD_S1") (pintype "passive"))
      (node (ref "J2") (pin "S2") (pinfunction "SHIELD_S2") (pintype "passive"))
      (node (ref "JP1") (pin "1") (pinfunction "1_1") (pintype "passive"))
      (node (ref "PB1") (pin "3") (pinfunction "MH_3") (pintype "passive"))
      (node (ref "PB1") (pin "4") (pinfunction "MH_4") (pintype "passive"))
      (node (ref "R1") (pin "2") (pinfunction "2_2") (pintype "passive"))
      (node (ref "R12") (pin "2") (pinfunction "2_2") (pintype "passive"))
      (node (ref "R19") (pin "2") (pinfunction "2_2") (pintype "passive"))
      (node (ref "R22") (pin "1") (pinfunction "1_1") (pintype "passive"))
      (node (ref "R23") (pin "1") (pinfunction "1_1") (pintype "passive"))
      (node (ref "R25") (pin "2") (pinfunction "2_2") (pintype "passive"))
      (node (ref "R26") (pin "1") (pinfunction "1_1") (pintype "passive"))
      (node (ref "R28") (pin "1") (pinfunction "1_1") (pintype "passive"))
      (node (ref "R34") (pin "1") (pinfunction "1_1") (pintype "passive"))
      (node (ref "R37") (pin "1") (pinfunction "1_1") (pintype "passive"))
      (node (ref "R38") (pin "1") (pinfunction "1_1") (pintype "passive"))
      (node (ref "R6") (pin "2") (pinfunction "2_2") (pintype "passive"))
      (node (ref "R7") (pin "2") (pinfunction "2_2") (pintype "passive"))
      (node (ref "R8") (pin "1") (pinfunction "1_1") (pintype "passive"))
      (node (ref "R9") (pin "1") (pinfunction "1_1") (pintype "passive"))
      (node (ref "T1") (pin "1") (pinfunction "1_1") (pintype "passive"))
      (node (ref "U1") (pin "27") (pinfunction "SENV−_27") (pintype "passive"))
      (node (ref "U1") (pin "31") (pinfunction "DVSS1_31") (pintype "passive"))
      (node (ref "U1") (pin "44") (pinfunction "AVSSP_44") (pintype "passive"))
      (node (ref "U1") (pin "45") (pinfunction "AVSSS_45") (pintype "passive"))
      (node (ref "U1") (pin "49") (pinfunction "TEST3_49") (pintype "passive"))
      (node (ref "U1") (pin "53") (pinfunction "TP_53") (pintype "passive"))
      (node (ref "U1") (pin "9") (pinfunction "DVSS2_9") (pintype "passive"))
      (node (ref "U4") (pin "AGND") (pinfunction "AGND_AGND") (pintype "passive"))
      (node (ref "U4") (pin "GND") (pinfunction "GND_GND") (pintype "passive"))
      (node (ref "U4") (pin "VSEL") (pinfunction "VSEL_VSEL") (pintype "passive"))
    )
    (net (code "23") (name "Net-(C4-Pad2)") (class "Default")
      (node (ref "C4") (pin "2") (pinfunction "2_2") (pintype "passive"))
      (node (ref "R13") (pin "1") (pinfunction "1_1") (pintype "passive"))
      (node (ref "U2") (pin "VCC") (pinfunction "VCC_VCC") (pintype "passive"))
    )
    (net (code "24") (name "Net-(C8-Pad2)") (class "Default")
      (node (ref "C8") (pin "2") (pinfunction "2_2") (pintype "passive"))
      (node (ref "R20") (pin "1") (pinfunction "1_1") (pintype "passive"))
      (node (ref "U3") (pin "VCC") (pinfunction "VCC_VCC") (pintype "passive"))
    )
    (net (code "25") (name "Net-(C16-Pad2)") (class "Default")
      (node (ref "C16") (pin "2") (pinfunction "2_2") (pintype "passive"))
      (node (ref "R27") (pin "2") (pinfunction "2_2") (pintype "passive"))
    )
    (net (code "26") (name "Net-(C25-Pad1)") (class "Default")
      (node (ref "C25") (pin "1") (pinfunction "1_1") (pintype "passive"))
      (node (ref "Q1") (pin "G") (pinfunction "G_G") (pintype "passive"))
      (node (ref "Q2") (pin "G") (pinfunction "G_G") (pintype "passive"))
      (node (ref "R30") (pin "2") (pinfunction "2_2") (pintype "passive"))
      (node (ref "R31") (pin "2") (pinfunction "2_2") (pintype "passive"))
    )
    (net (code "27") (name "Net-(C27-Pad2)") (class "Default")
      (node (ref "C27") (pin "2") (pinfunction "2_2") (pintype "passive"))
      (node (ref "L2") (pin "2") (pinfunction "2_2") (pintype "passive"))
      (node (ref "Q3") (pin "D") (pinfunction "D_D") (pintype "passive"))
    )
    (net (code "28") (name "Net-(C30-Pad2)") (class "Default")
      (node (ref "C30") (pin "2") (pinfunction "2_2") (pintype "passive"))
      (node (ref "Q4") (pin "G") (pinfunction "G_G") (pintype "passive"))
      (node (ref "Q5") (pin "G") (pinfunction "G_G") (pintype "passive"))
      (node (ref "R33") (pin "2") (pinfunction "2_2") (pintype "passive"))
      (node (ref "R34") (pin "2") (pinfunction "2_2") (pintype "passive"))
    )
    (net (code "29") (name "Net-(C31-Pad2)") (class "Default")
      (node (ref "C31") (pin "2") (pinfunction "2_2") (pintype "passive"))
      (node (ref "L4") (pin "2") (pinfunction "2_2") (pintype "passive"))
      (node (ref "Q6") (pin "D") (pinfunction "D_D") (pintype "passive"))
    )
    (net (code "30") (name "Net-(D1-ANODE1)") (class "Default")
      (node (ref "C3") (pin "2") (pinfunction "2_2") (pintype "passive"))
      (node (ref "D1") (pin "1") (pinfunction "ANODE1_1") (pintype "passive"))
      (node (ref "U1") (pin "41") (pinfunction "REGP_41") (pintype "passive"))
    )
    (net (code "31") (name "Net-(D4-cat)") (class "Default")
      (node (ref "D4") (pin "1") (pinfunction "cat_1") (pintype "passive"))
      (node (ref "R29") (pin "1") (pinfunction "1_1") (pintype "passive"))
    )
    (net (code "32") (name "Net-(L1-Pad1)") (class "Default")
      (node (ref "L1") (pin "1") (pinfunction "1_1") (pintype "passive"))
      (node (ref "U4") (pin "LX1") (pinfunction "LX1_LX1") (pintype "passive"))
    )
    (net (code "33") (name "Net-(L1-Pad2)") (class "Default")
      (node (ref "L1") (pin "2") (pinfunction "2_2") (pintype "passive"))
      (node (ref "U4") (pin "LX2") (pinfunction "LX2_LX2") (pintype "passive"))
    )
    (net (code "34") (name "Net-(L3-Pad1)") (class "Default")
      (node (ref "L3") (pin "1") (pinfunction "1_1") (pintype "passive"))
      (node (ref "Q1") (pin "D") (pinfunction "D_D") (pintype "passive"))
      (node (ref "Q2") (pin "D") (pinfunction "D_D") (pintype "passive"))
      (node (ref "Q4") (pin "D") (pinfunction "D_D") (pintype "passive"))
      (node (ref "Q5") (pin "D") (pinfunction "D_D") (pintype "passive"))
    )
    (net (code "35") (name "Net-(LED1-Anode)") (class "Default")
      (node (ref "LED1") (pin "2") (pinfunction "Anode_2") (pintype "passive"))
      (node (ref "R2") (pin "1") (pinfunction "1_1") (pintype "passive"))
    )
    (net (code "36") (name "Net-(LED1-Cathode)") (class "Default")
      (node (ref "LED1") (pin "1") (pinfunction "Cathode_1") (pintype "passive"))
      (node (ref "U1") (pin "20") (pinfunction "LED1_20") (pintype "passive"))
    )
    (net (code "37") (name "Net-(LED2-Anode)") (class "Default")
      (node (ref "LED2") (pin "2") (pinfunction "Anode_2") (pintype "passive"))
      (node (ref "R3") (pin "1") (pinfunction "1_1") (pintype "passive"))
    )
    (net (code "38") (name "Net-(LED2-Cathode)") (class "Default")
      (node (ref "LED2") (pin "1") (pinfunction "Cathode_1") (pintype "passive"))
      (node (ref "U1") (pin "21") (pinfunction "LED2_21") (pintype "passive"))
    )
    (net (code "39") (name "Net-(LED3-Anode)") (class "Default")
      (node (ref "LED3") (pin "2") (pinfunction "Anode_2") (pintype "passive"))
      (node (ref "R4") (pin "1") (pinfunction "1_1") (pintype "passive"))
    )
    (net (code "40") (name "Net-(LED3-Cathode)") (class "Default")
      (node (ref "LED3") (pin "1") (pinfunction "Cathode_1") (pintype "passive"))
      (node (ref "U1") (pin "22") (pinfunction "LED3_22") (pintype "passive"))
    )
    (net (code "41") (name "Net-(LED4-Anode)") (class "Default")
      (node (ref "LED4") (pin "2") (pinfunction "Anode_2") (pintype "passive"))
      (node (ref "R5") (pin "1") (pinfunction "1_1") (pintype "passive"))
    )
    (net (code "42") (name "Net-(LED4-Cathode)") (class "Default")
      (node (ref "LED4") (pin "1") (pinfunction "Cathode_1") (pintype "passive"))
      (node (ref "U1") (pin "23") (pinfunction "LED4_23") (pintype "passive"))
    )
    (net (code "43") (name "Net-(R11-Pad1)") (class "Default")
      (node (ref "R11") (pin "1") (pinfunction "1_1") (pintype "passive"))
      (node (ref "U2") (pin "CS") (pinfunction "CS_CS") (pintype "passive"))
    )
    (net (code "44") (name "Net-(R14-Pad2)") (class "Default")
      (node (ref "R14") (pin "2") (pinfunction "2_2") (pintype "passive"))
      (node (ref "R15") (pin "2") (pinfunction "2_2") (pintype "passive"))
      (node (ref "T1") (pin "2") (pinfunction "2_2") (pintype "passive"))
    )
    (net (code "45") (name "Net-(R18-Pad1)") (class "Default")
      (node (ref "R18") (pin "1") (pinfunction "1_1") (pintype "passive"))
      (node (ref "U3") (pin "CS") (pinfunction "CS_CS") (pintype "passive"))
    )
    (net (code "46") (name "Net-(U1-BATSEL)") (class "Default")
      (node (ref "R8") (pin "2") (pinfunction "2_2") (pintype "passive"))
      (node (ref "U1") (pin "11") (pinfunction "BATSEL_11") (pintype "passive"))
    )
    (net (code "47") (name "Net-(U1-COMPU)") (class "Default")
      (node (ref "C15") (pin "2") (pinfunction "2_2") (pintype "passive"))
      (node (ref "R27") (pin "1") (pinfunction "1_1") (pintype "passive"))
      (node (ref "U1") (pin "39") (pinfunction "COMPU_39") (pintype "passive"))
    )
    (net (code "48") (name "Net-(U1-FGADJ)") (class "Default")
      (node (ref "R6") (pin "1") (pinfunction "1_1") (pintype "passive"))
      (node (ref "U1") (pin "10") (pinfunction "FGADJ_10") (pintype "passive"))
    )
    (net (code "49") (name "Net-(U1-IBTSEL)") (class "Default")
      (node (ref "R9") (pin "2") (pinfunction "2_2") (pintype "passive"))
      (node (ref "U1") (pin "13") (pinfunction "IBTSEL_13") (pintype "passive"))
    )
    (net (code "50") (name "Net-(U1-PBT)") (class "Default")
      (node (ref "C2") (pin "2") (pinfunction "2_2") (pintype "passive"))
      (node (ref "PB1") (pin "2") (pinfunction "2_2") (pintype "passive"))
      (node (ref "R7") (pin "1") (pinfunction "1_1") (pintype "passive"))
      (node (ref "U1") (pin "8") (pinfunction "PBT_8") (pintype "passive"))
    )
    (net (code "51") (name "Net-(U1-REG33)") (class "Default")
      (node (ref "C1") (pin "2") (pinfunction "2_2") (pintype "passive"))
      (node (ref "U1") (pin "7") (pinfunction "REG33_7") (pintype "passive"))
    )
    (net (code "52") (name "Net-(U1-REGN)") (class "Default")
      (node (ref "C17") (pin "1") (pinfunction "1_1") (pintype "passive"))
      (node (ref "U1") (pin "47") (pinfunction "REGN_47") (pintype "passive"))
    )
    (net (code "53") (name "Net-(U1-SENB+)") (class "Default")
      (node (ref "C9") (pin "2") (pinfunction "2_2") (pintype "passive"))
      (node (ref "R21") (pin "1") (pinfunction "1_1") (pintype "passive"))
      (node (ref "U1") (pin "33") (pinfunction "SENB+_33") (pintype "passive"))
    )
    (net (code "54") (name "Net-(U1-SENB−)") (class "Default")
      (node (ref "C9") (pin "1") (pinfunction "1_1") (pintype "passive"))
      (node (ref "R25") (pin "1") (pinfunction "1_1") (pintype "passive"))
      (node (ref "U1") (pin "34") (pinfunction "SENB−_34") (pintype "passive"))
    )
    (net (code "55") (name "Net-(U1-SENV1+)") (class "Default")
      (node (ref "R10") (pin "2") (pinfunction "2_2") (pintype "passive"))
      (node (ref "U1") (pin "24") (pinfunction "SENV1+_24") (pintype "passive"))
    )
    (net (code "56") (name "Net-(U1-SENV3+)") (class "Default")
      (node (ref "R17") (pin "2") (pinfunction "2_2") (pintype "passive"))
      (node (ref "U1") (pin "26") (pinfunction "SENV3+_26") (pintype "passive"))
    )
    (net (code "57") (name "Net-(U1-TSENSE)") (class "Default")
      (node (ref "R15") (pin "1") (pinfunction "1_1") (pintype "passive"))
      (node (ref "U1") (pin "38") (pinfunction "TSENSE_38") (pintype "passive"))
    )
    (net (code "58") (name "Net-(U1-TSW)") (class "Default")
      (node (ref "R14") (pin "1") (pinfunction "1_1") (pintype "passive"))
      (node (ref "U1") (pin "37") (pinfunction "TSW_37") (pintype "passive"))
    )
    (net (code "59") (name "Net-(U1-VB3DET)") (class "Default")
      (node (ref "C10") (pin "2") (pinfunction "2_2") (pintype "passive"))
      (node (ref "R24") (pin "1") (pinfunction "1_1") (pintype "passive"))
      (node (ref "R26") (pin "2") (pinfunction "2_2") (pintype "passive"))
      (node (ref "U1") (pin "15") (pinfunction "VB3DET_15") (pintype "passive"))
    )
    (net (code "60") (name "Net-(U1-VBAT)") (class "Default")
      (node (ref "C7") (pin "2") (pinfunction "2_2") (pintype "passive"))
      (node (ref "R16") (pin "1") (pinfunction "1_1") (pintype "passive"))
      (node (ref "U1") (pin "32") (pinfunction "VBAT_32") (pintype "passive"))
    )
    (net (code "61") (name "VBUS_A") (class "Default")
      (node (ref "C26") (pin "2") (pinfunction "2_2") (pintype "passive"))
      (node (ref "J2") (pin "1") (pinfunction "VBUS_1") (pintype "passive"))
      (node (ref "L2") (pin "1") (pinfunction "1_1") (pintype "passive"))
      (node (ref "R24") (pin "2") (pinfunction "2_2") (pintype "passive"))
    )
    (net (code "62") (name "VBUS_C") (class "Default")
      (node (ref "C33") (pin "2") (pinfunction "2_2") (pintype "passive"))
      (node (ref "J1") (pin "A4") (pinfunction "VBUS_A4_A4") (pintype "passive"))
      (node (ref "J1") (pin "A9") (pinfunction "VBUS_A9_A9") (pintype "passive"))
      (node (ref "J1") (pin "B4") (pinfunction "VBUS_B4_B4") (pintype "passive"))
      (node (ref "J1") (pin "B9") (pinfunction "VBUS_B9_B9") (pintype "passive"))
      (node (ref "L4") (pin "1") (pinfunction "1_1") (pintype "passive"))
      (node (ref "R35") (pin "2") (pinfunction "2_2") (pintype "passive"))
    )
    (net (code "63") (name "VCC") (class "Default")
      (node (ref "C17") (pin "2") (pinfunction "2_2") (pintype "passive"))
      (node (ref "C18") (pin "2") (pinfunction "2_2") (pintype "passive"))
      (node (ref "C19") (pin "2") (pinfunction "2_2") (pintype "passive"))
      (node (ref "C20") (pin "2") (pinfunction "2_2") (pintype "passive"))
      (node (ref "C21") (pin "2") (pinfunction "2_2") (pintype "passive"))
      (node (ref "C22") (pin "2") (pinfunction "2_2") (pintype "passive"))
      (node (ref "C23") (pin "2") (pinfunction "2_2") (pintype "passive"))
      (node (ref "C24") (pin "2") (pinfunction "2_2") (pintype "passive"))
      (node (ref "C25") (pin "2") (pinfunction "2_2") (pintype "passive"))
      (node (ref "Q1") (pin "S") (pinfunction "S_S") (pintype "passive"))
      (node (ref "Q2") (pin "S") (pinfunction "S_S") (pintype "passive"))
      (node (ref "Q6") (pin "S") (pinfunction "S_S") (pintype "passive"))
      (node (ref "R30") (pin "1") (pinfunction "1_1") (pintype "passive"))
      (node (ref "R36") (pin "2") (pinfunction "2_2") (pintype "passive"))
      (node (ref "U1") (pin "40") (pinfunction "VCC_REG_40") (pintype "passive"))
      (node (ref "U1") (pin "48") (pinfunction "VCC_48") (pintype "passive"))
    )
    (net (code "64") (name "unconnected-(MH1-Pad1)") (class "Default")
      (node (ref "MH1") (pin "1") (pinfunction "1_1") (pintype "passive+no_connect"))
    )
    (net (code "65") (name "unconnected-(MH2-Pad1)") (class "Default")
      (node (ref "MH2") (pin "1") (pinfunction "1_1") (pintype "passive+no_connect"))
    )
    (net (code "66") (name "unconnected-(MH3-Pad1)") (class "Default")
      (node (ref "MH3") (pin "1") (pinfunction "1_1") (pintype "passive+no_connect"))
    )
    (net (code "67") (name "unconnected-(MH4-Pad1)") (class "Default")
      (node (ref "MH4") (pin "1") (pinfunction "1_1") (pintype "passive+no_connect"))
    )
    (net (code "68") (name "unconnected-(U1-GATE2-Pad51)") (class "Default")
      (node (ref "U1") (pin "51") (pinfunction "GATE2_51") (pintype "passive+no_connect"))
    )
    (net (code "69") (name "unconnected-(U1-SENV2+-Pad25)") (class "Default")
      (node (ref "U1") (pin "25") (pinfunction "SENV2+_25") (pintype "passive+no_connect"))
    )
    (net (code "70") (name "unconnected-(U1-TEST2-Pad36)") (class "Default")
      (node (ref "U1") (pin "36") (pinfunction "TEST2_36") (pintype "passive+no_connect"))
    )
    (net (code "71") (name "unconnected-(U1-USB2+-Pad6)") (class "Default")
      (node (ref "U1") (pin "6") (pinfunction "USB2+_6") (pintype "passive+no_connect"))
    )
    (net (code "72") (name "unconnected-(U1-USB2--Pad5)") (class "Default")
      (node (ref "U1") (pin "5") (pinfunction "USB2-_5") (pintype "passive+no_connect"))
    )
    (net (code "73") (name "unconnected-(U1-VB2DET-Pad14)") (class "Default")
      (node (ref "U1") (pin "14") (pinfunction "VB2DET_14") (pintype "passive+no_connect"))
    )
    (net (code "74") (name "unconnected-(U1-VBUS2-Pad2)") (class "Default")
      (node (ref "U1") (pin "2") (pinfunction "VBUS2_2") (pintype "passive+no_connect"))
    )
    (net (code "75") (name "unconnected-(U1-XT1-Pad29)") (class "Default")
      (node (ref "U1") (pin "29") (pinfunction "XT1_29") (pintype "passive+no_connect"))
    )
    (net (code "76") (name "unconnected-(U1-XT2-Pad30)") (class "Default")
      (node (ref "U1") (pin "30") (pinfunction "XT2_30") (pintype "passive+no_connect"))
    )
    (net (code "77") (name "unconnected-(U2-PadD)") (class "Default")
      (node (ref "U2") (pin "D") (pinfunction "D_D") (pintype "passive+no_connect"))
    )
    (net (code "78") (name "unconnected-(U2-PadSUB)") (class "Default")
      (node (ref "U2") (pin "SUB") (pinfunction "SUB_SUB") (pintype "passive+no_connect"))
    )
    (net (code "79") (name "unconnected-(U3-PadD)") (class "Default")
      (node (ref "U3") (pin "D") (pinfunction "D_D") (pintype "passive+no_connect"))
    )
    (net (code "80") (name "unconnected-(U3-PadSUB)") (class "Default")
      (node (ref "U3") (pin "SUB") (pinfunction "SUB_SUB") (pintype "passive+no_connect"))
    )
    (net (code "81") (name "unconnected-(U4-PadSCL)") (class "Default")
      (node (ref "U4") (pin "SCL") (pinfunction "SCL_SCL") (pintype "passive+no_connect"))
    )
    (net (code "82") (name "unconnected-(U4-PadSDA)") (class "Default")
      (node (ref "U4") (pin "SDA") (pinfunction "SDA_SDA") (pintype "passive+no_connect"))
    )
  )
)
